# rocket_pack-compact.net
KiCad netlist of a schematic drawn in EAGLE
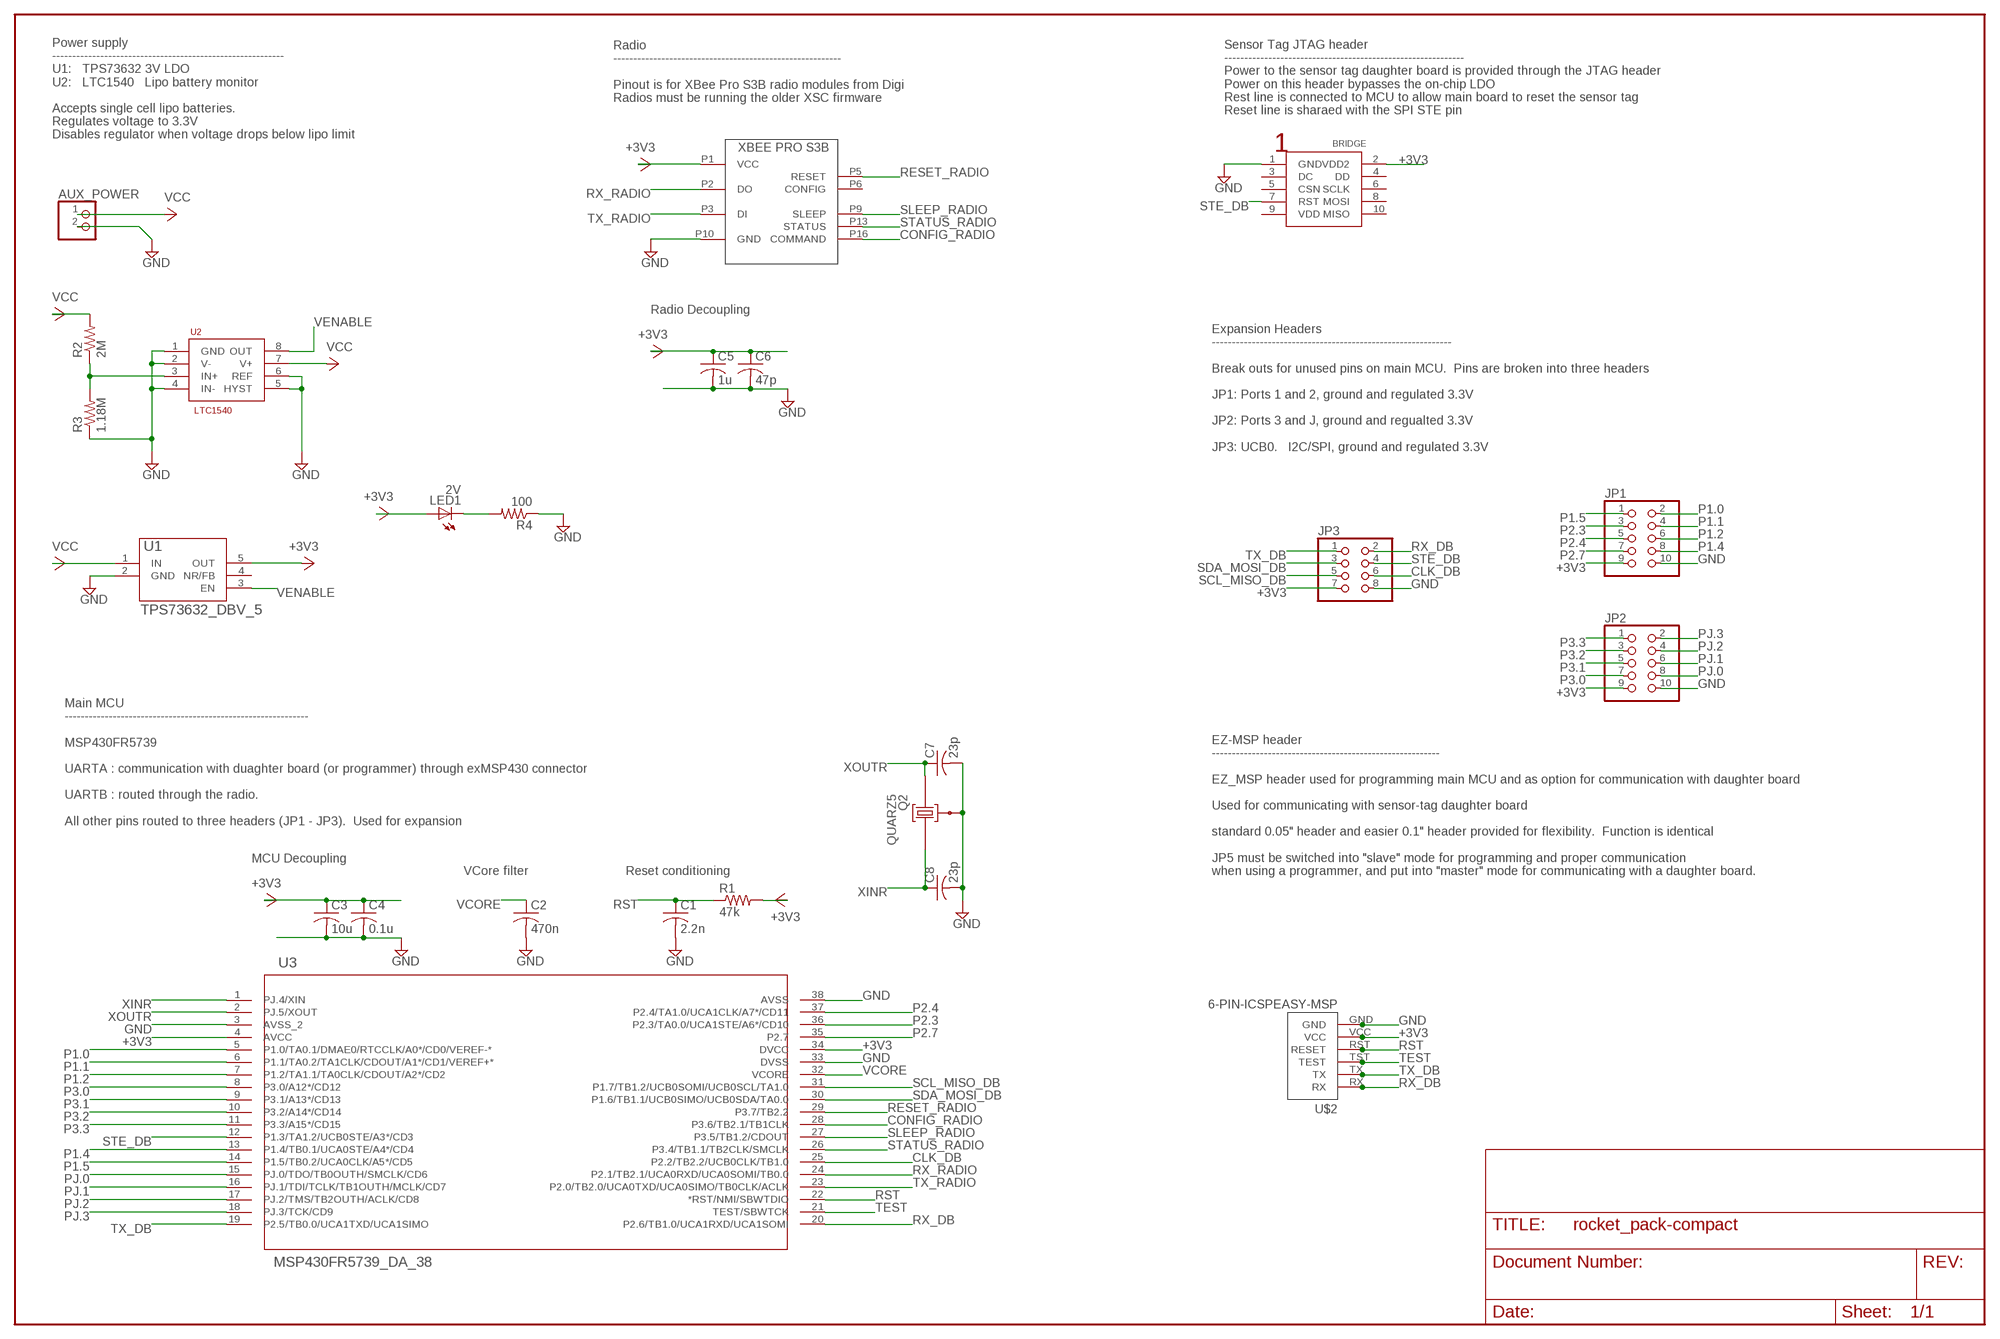
[diagram p0: schematic, sheet 1]

(export (version "E")
  (design (tool "Eeschema 10.0.6"))
  (components
    (comp (ref "AUX_POWER")
      (value "PINHD-1X2")
      (footprint "eagle-import:1X02")
      (libsource (lib "eagle-import") (part "PINHD-1X2"))
    )
    (comp (ref "BRIDGE")
      (value "CC-DEBUG")
      (footprint "eagle-import:2X5-1.27MM")
      (libsource (lib "eagle-import") (part "CC-DEBUG"))
    )
    (comp (ref "C1")
      (value "2.2n")
      (footprint "eagle-import:C1206")
      (libsource (lib "eagle-import") (part "C-USC1206"))
    )
    (comp (ref "C2")
      (value "470n")
      (footprint "eagle-import:C1206")
      (libsource (lib "eagle-import") (part "C-USC1206"))
    )
    (comp (ref "C3")
      (value "10u")
      (footprint "eagle-import:C1206")
      (libsource (lib "eagle-import") (part "C-USC1206"))
    )
    (comp (ref "C4")
      (value "0.1u")
      (footprint "eagle-import:C1206")
      (libsource (lib "eagle-import") (part "C-USC1206"))
    )
    (comp (ref "C5")
      (value "1u")
      (footprint "eagle-import:C1206")
      (libsource (lib "eagle-import") (part "C-USC1206"))
    )
    (comp (ref "C6")
      (value "47p")
      (footprint "eagle-import:C1206")
      (libsource (lib "eagle-import") (part "C-USC1206"))
    )
    (comp (ref "C7")
      (value "23p")
      (footprint "eagle-import:C1206")
      (libsource (lib "eagle-import") (part "C-USC1206"))
    )
    (comp (ref "C8")
      (value "23p")
      (footprint "eagle-import:C1206")
      (libsource (lib "eagle-import") (part "C-USC1206"))
    )
    (comp (ref "JP1")
      (value "PINHD-2X5")
      (footprint "eagle-import:2X05")
      (libsource (lib "eagle-import") (part "PINHD-2X5"))
    )
    (comp (ref "JP2")
      (value "PINHD-2X5")
      (footprint "eagle-import:2X05")
      (libsource (lib "eagle-import") (part "PINHD-2X5"))
    )
    (comp (ref "JP3")
      (value "PINHD-2X4")
      (footprint "eagle-import:2X04")
      (libsource (lib "eagle-import") (part "PINHD-2X4"))
    )
    (comp (ref "LED1")
      (value "2V")
      (footprint "eagle-import:1206")
      (libsource (lib "eagle-import") (part "LEDSMT1206"))
    )
    (comp (ref "Q2")
      (value "QUARZ5")
      (footprint "eagle-import:QUARZ5")
      (libsource (lib "eagle-import") (part "QUARZ5"))
    )
    (comp (ref "R1")
      (value "47k")
      (footprint "eagle-import:R1206")
      (libsource (lib "eagle-import") (part "R-US_R1206"))
    )
    (comp (ref "R2")
      (value "2M")
      (footprint "eagle-import:R1206")
      (libsource (lib "eagle-import") (part "R-US_R1206"))
    )
    (comp (ref "R3")
      (value "1.18M")
      (footprint "eagle-import:R1206")
      (libsource (lib "eagle-import") (part "R-US_R1206"))
    )
    (comp (ref "R4")
      (value "100")
      (footprint "eagle-import:R1206")
      (libsource (lib "eagle-import") (part "R-US_R1206"))
    )
    (comp (ref "U$1")
      (value "XBEE_PRO_S3B")
      (footprint "eagle-import:PRO_S3B")
      (libsource (lib "eagle-import") (part "XBEE_PRO_S3B"))
    )
    (comp (ref "U$2")
      (value "6-PIN-ICSPEASY-MSP")
      (footprint "eagle-import:EASYMSP-6PIN")
      (libsource (lib "eagle-import") (part "6-PIN-ICSPEASY-MSP"))
    )
    (comp (ref "U1")
      (value "TPS73632_DBV_5")
      (footprint "eagle-import:DBV5")
      (fields
        (field (name "GENERIC_PART_NUMBER") "TPS73632")
        (field (name "MANUFACTURER") "Texas Instruments")
        (field (name "MANUFACTURER_PART_NUMBER") "tps73632_dbv_5")
      )
      (libsource (lib "eagle-import") (part "TPS73632_DBV_5"))
    )
    (comp (ref "U2")
      (value "LTC1540")
      (footprint "eagle-import:S8")
      (libsource (lib "eagle-import") (part "LTC1540"))
    )
    (comp (ref "U3")
      (value "MSP430FR5739_DA_38")
      (footprint "eagle-import:DA38")
      (fields
        (field (name "GENERIC_PART_NUMBER") "MSP430FR5739")
        (field (name "MANUFACTURER") "Texas Instruments")
        (field (name "MANUFACTURER_PART_NUMBER") "msp430fr5739_da_38")
      )
      (libsource (lib "eagle-import") (part "MSP430FR5739_DA_38"))
    )
  )
  (nets
    (net (code "1") (name "+3V3") (class "Default")
      (node (ref "BRIDGE") (pin "2") (pinfunction "VDD2_2") (pintype "bidirectional"))
      (node (ref "C3") (pin "1") (pinfunction "1_1") (pintype "passive"))
      (node (ref "C4") (pin "1") (pinfunction "1_1") (pintype "passive"))
      (node (ref "C5") (pin "1") (pinfunction "1_1") (pintype "passive"))
      (node (ref "C6") (pin "1") (pinfunction "1_1") (pintype "passive"))
      (node (ref "JP1") (pin "9") (pinfunction "9_9") (pintype "passive"))
      (node (ref "JP2") (pin "9") (pinfunction "9_9") (pintype "passive"))
      (node (ref "JP3") (pin "7") (pinfunction "7_7") (pintype "passive"))
      (node (ref "LED1") (pin "A") (pinfunction "A_A") (pintype "passive"))
      (node (ref "R1") (pin "2") (pinfunction "2_2") (pintype "passive"))
      (node (ref "U$1") (pin "P1") (pinfunction "VCC_P1") (pintype "bidirectional"))
      (node (ref "U$2") (pin "VCC") (pinfunction "VCC_VCC") (pintype "bidirectional"))
      (node (ref "U1") (pin "5") (pinfunction "OUT_5") (pintype "output"))
      (node (ref "U3") (pin "34") (pinfunction "DVCC_34") (pintype "power_in"))
      (node (ref "U3") (pin "4") (pinfunction "AVCC_4") (pintype "power_in"))
    )
    (net (code "2") (name "/CLK_DB") (class "Default")
      (node (ref "JP3") (pin "6") (pinfunction "6_6") (pintype "passive"))
      (node (ref "U3") (pin "25") (pinfunction "P2.2/TB2.2/UCB0CLK/TB1.0_25") (pintype "bidirectional"))
    )
    (net (code "3") (name "/CONFIG_RADIO") (class "Default")
      (node (ref "U$1") (pin "P16") (pinfunction "COMMAND_P16") (pintype "bidirectional"))
      (node (ref "U3") (pin "28") (pinfunction "P3.6/TB2.1/TB1CLK_28") (pintype "bidirectional"))
    )
    (net (code "4") (name "/P1.0") (class "Default")
      (node (ref "JP1") (pin "2") (pinfunction "2_2") (pintype "passive"))
      (node (ref "U3") (pin "5") (pinfunction "P1.0/TA0.1/DMAE0/RTCCLK/A0*/CD0/VEREF-*_5") (pintype "bidirectional"))
    )
    (net (code "5") (name "/P1.1") (class "Default")
      (node (ref "JP1") (pin "4") (pinfunction "4_4") (pintype "passive"))
      (node (ref "U3") (pin "6") (pinfunction "P1.1/TA0.2/TA1CLK/CDOUT/A1*/CD1/VEREF+*_6") (pintype "bidirectional"))
    )
    (net (code "6") (name "/P1.2") (class "Default")
      (node (ref "JP1") (pin "6") (pinfunction "6_6") (pintype "passive"))
      (node (ref "U3") (pin "7") (pinfunction "P1.2/TA1.1/TA0CLK/CDOUT/A2*/CD2_7") (pintype "bidirectional"))
    )
    (net (code "7") (name "/P1.4") (class "Default")
      (node (ref "JP1") (pin "8") (pinfunction "8_8") (pintype "passive"))
      (node (ref "U3") (pin "13") (pinfunction "P1.4/TB0.1/UCA0STE/A4*/CD4_13") (pintype "bidirectional"))
    )
    (net (code "8") (name "/P1.5") (class "Default")
      (node (ref "JP1") (pin "1") (pinfunction "1_1") (pintype "passive"))
      (node (ref "U3") (pin "14") (pinfunction "P1.5/TB0.2/UCA0CLK/A5*/CD5_14") (pintype "bidirectional"))
    )
    (net (code "9") (name "/P2.3") (class "Default")
      (node (ref "JP1") (pin "3") (pinfunction "3_3") (pintype "passive"))
      (node (ref "U3") (pin "36") (pinfunction "P2.3/TA0.0/UCA1STE/A6*/CD10_36") (pintype "bidirectional"))
    )
    (net (code "10") (name "/P2.4") (class "Default")
      (node (ref "JP1") (pin "5") (pinfunction "5_5") (pintype "passive"))
      (node (ref "U3") (pin "37") (pinfunction "P2.4/TA1.0/UCA1CLK/A7*/CD11_37") (pintype "bidirectional"))
    )
    (net (code "11") (name "/P2.7") (class "Default")
      (node (ref "JP1") (pin "7") (pinfunction "7_7") (pintype "passive"))
      (node (ref "U3") (pin "35") (pinfunction "P2.7_35") (pintype "bidirectional"))
    )
    (net (code "12") (name "/P3.0") (class "Default")
      (node (ref "JP2") (pin "7") (pinfunction "7_7") (pintype "passive"))
      (node (ref "U3") (pin "8") (pinfunction "P3.0/A12*/CD12_8") (pintype "bidirectional"))
    )
    (net (code "13") (name "/P3.1") (class "Default")
      (node (ref "JP2") (pin "5") (pinfunction "5_5") (pintype "passive"))
      (node (ref "U3") (pin "9") (pinfunction "P3.1/A13*/CD13_9") (pintype "bidirectional"))
    )
    (net (code "14") (name "/P3.2") (class "Default")
      (node (ref "JP2") (pin "3") (pinfunction "3_3") (pintype "passive"))
      (node (ref "U3") (pin "10") (pinfunction "P3.2/A14*/CD14_10") (pintype "bidirectional"))
    )
    (net (code "15") (name "/P3.3") (class "Default")
      (node (ref "JP2") (pin "1") (pinfunction "1_1") (pintype "passive"))
      (node (ref "U3") (pin "11") (pinfunction "P3.3/A15*/CD15_11") (pintype "bidirectional"))
    )
    (net (code "16") (name "/PJ.0") (class "Default")
      (node (ref "JP2") (pin "8") (pinfunction "8_8") (pintype "passive"))
      (node (ref "U3") (pin "15") (pinfunction "PJ.0/TDO/TB0OUTH/SMCLK/CD6_15") (pintype "bidirectional"))
    )
    (net (code "17") (name "/PJ.1") (class "Default")
      (node (ref "JP2") (pin "6") (pinfunction "6_6") (pintype "passive"))
      (node (ref "U3") (pin "16") (pinfunction "PJ.1/TDI/TCLK/TB1OUTH/MCLK/CD7_16") (pintype "bidirectional"))
    )
    (net (code "18") (name "/PJ.2") (class "Default")
      (node (ref "JP2") (pin "4") (pinfunction "4_4") (pintype "passive"))
      (node (ref "U3") (pin "17") (pinfunction "PJ.2/TMS/TB2OUTH/ACLK/CD8_17") (pintype "bidirectional"))
    )
    (net (code "19") (name "/PJ.3") (class "Default")
      (node (ref "JP2") (pin "2") (pinfunction "2_2") (pintype "passive"))
      (node (ref "U3") (pin "18") (pinfunction "PJ.3/TCK/CD9_18") (pintype "bidirectional"))
    )
    (net (code "20") (name "/RESET_RADIO") (class "Default")
      (node (ref "U$1") (pin "P5") (pinfunction "RESET_P5") (pintype "bidirectional"))
      (node (ref "U3") (pin "29") (pinfunction "P3.7/TB2.2_29") (pintype "bidirectional"))
    )
    (net (code "21") (name "/RST") (class "Default")
      (node (ref "C1") (pin "1") (pinfunction "1_1") (pintype "passive"))
      (node (ref "R1") (pin "1") (pinfunction "1_1") (pintype "passive"))
      (node (ref "U$2") (pin "RST") (pinfunction "RESET_RST") (pintype "bidirectional"))
      (node (ref "U3") (pin "22") (pinfunction "*RST/NMI/SBWTDIO_22") (pintype "bidirectional"))
    )
    (net (code "22") (name "/RX_DB") (class "Default")
      (node (ref "JP3") (pin "2") (pinfunction "2_2") (pintype "passive"))
      (node (ref "U$2") (pin "RX") (pinfunction "RX_RX") (pintype "bidirectional"))
      (node (ref "U3") (pin "20") (pinfunction "P2.6/TB1.0/UCA1RXD/UCA1SOMI_20") (pintype "bidirectional"))
    )
    (net (code "23") (name "/RX_RADIO") (class "Default")
      (node (ref "U$1") (pin "P2") (pinfunction "DO_P2") (pintype "bidirectional"))
      (node (ref "U3") (pin "24") (pinfunction "P2.1/TB2.1/UCA0RXD/UCA0SOMI/TB0.0_24") (pintype "bidirectional"))
    )
    (net (code "24") (name "/SCL_MISO_DB") (class "Default")
      (node (ref "JP3") (pin "5") (pinfunction "5_5") (pintype "passive"))
      (node (ref "U3") (pin "31") (pinfunction "P1.7/TB1.2/UCB0SOMI/UCB0SCL/TA1.0_31") (pintype "bidirectional"))
    )
    (net (code "25") (name "/SDA_MOSI_DB") (class "Default")
      (node (ref "JP3") (pin "3") (pinfunction "3_3") (pintype "passive"))
      (node (ref "U3") (pin "30") (pinfunction "P1.6/TB1.1/UCB0SIMO/UCB0SDA/TA0.0_30") (pintype "bidirectional"))
    )
    (net (code "26") (name "/SLEEP_RADIO") (class "Default")
      (node (ref "U$1") (pin "P9") (pinfunction "SLEEP_P9") (pintype "bidirectional"))
      (node (ref "U3") (pin "27") (pinfunction "P3.5/TB1.2/CDOUT_27") (pintype "bidirectional"))
    )
    (net (code "27") (name "/STATUS_RADIO") (class "Default")
      (node (ref "U$1") (pin "P13") (pinfunction "STATUS_P13") (pintype "bidirectional"))
      (node (ref "U3") (pin "26") (pinfunction "P3.4/TB1.1/TB2CLK/SMCLK_26") (pintype "bidirectional"))
    )
    (net (code "28") (name "/STE_DB") (class "Default")
      (node (ref "BRIDGE") (pin "7") (pinfunction "RST_7") (pintype "bidirectional"))
      (node (ref "JP3") (pin "4") (pinfunction "4_4") (pintype "passive"))
      (node (ref "U3") (pin "12") (pinfunction "P1.3/TA1.2/UCB0STE/A3*/CD3_12") (pintype "bidirectional"))
    )
    (net (code "29") (name "/TEST") (class "Default")
      (node (ref "U$2") (pin "TST") (pinfunction "TEST_TST") (pintype "bidirectional"))
      (node (ref "U3") (pin "21") (pinfunction "TEST/SBWTCK_21") (pintype "bidirectional"))
    )
    (net (code "30") (name "/TX_DB") (class "Default")
      (node (ref "JP3") (pin "1") (pinfunction "1_1") (pintype "passive"))
      (node (ref "U$2") (pin "TX") (pinfunction "TX_TX") (pintype "bidirectional"))
      (node (ref "U3") (pin "19") (pinfunction "P2.5/TB0.0/UCA1TXD/UCA1SIMO_19") (pintype "bidirectional"))
    )
    (net (code "31") (name "/TX_RADIO") (class "Default")
      (node (ref "U$1") (pin "P3") (pinfunction "DI_P3") (pintype "bidirectional"))
      (node (ref "U3") (pin "23") (pinfunction "P2.0/TB2.0/UCA0TXD/UCA0SIMO/TB0CLK/ACLK_23") (pintype "bidirectional"))
    )
    (net (code "32") (name "/VCORE") (class "Default")
      (node (ref "C2") (pin "1") (pinfunction "1_1") (pintype "passive"))
      (node (ref "U3") (pin "32") (pinfunction "VCORE_32") (pintype "power_in"))
    )
    (net (code "33") (name "/VENABLE") (class "Default")
      (node (ref "U1") (pin "3") (pinfunction "EN_3") (pintype "passive"))
      (node (ref "U2") (pin "8") (pinfunction "OUT_8") (pintype "bidirectional"))
    )
    (net (code "34") (name "/XINR") (class "Default")
      (node (ref "C8") (pin "1") (pinfunction "1_1") (pintype "passive"))
      (node (ref "Q2") (pin "1") (pinfunction "1_1") (pintype "passive"))
      (node (ref "U3") (pin "1") (pinfunction "PJ.4/XIN_1") (pintype "bidirectional"))
    )
    (net (code "35") (name "/XOUTR") (class "Default")
      (node (ref "C7") (pin "1") (pinfunction "1_1") (pintype "passive"))
      (node (ref "Q2") (pin "2") (pinfunction "2_2") (pintype "passive"))
      (node (ref "U3") (pin "2") (pinfunction "PJ.5/XOUT_2") (pintype "bidirectional"))
    )
    (net (code "36") (name "GND") (class "Default")
      (node (ref "AUX_POWER") (pin "2") (pinfunction "2_2") (pintype "passive"))
      (node (ref "BRIDGE") (pin "1") (pinfunction "GND_1") (pintype "bidirectional"))
      (node (ref "C1") (pin "2") (pinfunction "2_2") (pintype "passive"))
      (node (ref "C2") (pin "2") (pinfunction "2_2") (pintype "passive"))
      (node (ref "C3") (pin "2") (pinfunction "2_2") (pintype "passive"))
      (node (ref "C4") (pin "2") (pinfunction "2_2") (pintype "passive"))
      (node (ref "C5") (pin "2") (pinfunction "2_2") (pintype "passive"))
      (node (ref "C6") (pin "2") (pinfunction "2_2") (pintype "passive"))
      (node (ref "C7") (pin "2") (pinfunction "2_2") (pintype "passive"))
      (node (ref "C8") (pin "2") (pinfunction "2_2") (pintype "passive"))
      (node (ref "JP1") (pin "10") (pinfunction "10_10") (pintype "passive"))
      (node (ref "JP2") (pin "10") (pinfunction "10_10") (pintype "passive"))
      (node (ref "JP3") (pin "8") (pinfunction "8_8") (pintype "passive"))
      (node (ref "Q2") (pin "GND@0") (pinfunction "0_GND@0") (pintype "passive"))
      (node (ref "R3") (pin "1") (pinfunction "1_1") (pintype "passive"))
      (node (ref "R4") (pin "1") (pinfunction "1_1") (pintype "passive"))
      (node (ref "U$1") (pin "P10") (pinfunction "GND_P10") (pintype "bidirectional"))
      (node (ref "U$2") (pin "GND") (pinfunction "GND_GND") (pintype "bidirectional"))
      (node (ref "U1") (pin "2") (pinfunction "GND_2") (pintype "power_in"))
      (node (ref "U2") (pin "1") (pinfunction "GND_1") (pintype "bidirectional"))
      (node (ref "U2") (pin "2") (pinfunction "V-_2") (pintype "bidirectional"))
      (node (ref "U2") (pin "4") (pinfunction "IN-_4") (pintype "bidirectional"))
      (node (ref "U2") (pin "5") (pinfunction "HYST_5") (pintype "bidirectional"))
      (node (ref "U2") (pin "6") (pinfunction "REF_6") (pintype "bidirectional"))
      (node (ref "U3") (pin "3") (pinfunction "AVSS_2_3") (pintype "power_in"))
      (node (ref "U3") (pin "33") (pinfunction "DVSS_33") (pintype "power_in"))
      (node (ref "U3") (pin "38") (pinfunction "AVSS_38") (pintype "power_in"))
    )
    (net (code "37") (name "Net-(LED1-PadC)") (class "Default")
      (node (ref "LED1") (pin "C") (pinfunction "C_C") (pintype "passive"))
      (node (ref "R4") (pin "2") (pinfunction "2_2") (pintype "passive"))
    )
    (net (code "38") (name "Net-(U2-IN+)") (class "Default")
      (node (ref "R2") (pin "1") (pinfunction "1_1") (pintype "passive"))
      (node (ref "R3") (pin "2") (pinfunction "2_2") (pintype "passive"))
      (node (ref "U2") (pin "3") (pinfunction "IN+_3") (pintype "bidirectional"))
    )
    (net (code "39") (name "VCC") (class "Default")
      (node (ref "AUX_POWER") (pin "1") (pinfunction "1_1") (pintype "passive"))
      (node (ref "R2") (pin "2") (pinfunction "2_2") (pintype "passive"))
      (node (ref "U1") (pin "1") (pinfunction "IN_1") (pintype "input"))
      (node (ref "U2") (pin "7") (pinfunction "V+_7") (pintype "bidirectional"))
    )
    (net (code "40") (name "unconnected-(BRIDGE-CSN-Pad5)") (class "Default")
      (node (ref "BRIDGE") (pin "5") (pinfunction "CSN_5") (pintype "bidirectional"))
    )
    (net (code "41") (name "unconnected-(BRIDGE-DC-Pad3)") (class "Default")
      (node (ref "BRIDGE") (pin "3") (pinfunction "DC_3") (pintype "bidirectional"))
    )
    (net (code "42") (name "unconnected-(BRIDGE-DD-Pad4)") (class "Default")
      (node (ref "BRIDGE") (pin "4") (pinfunction "DD_4") (pintype "bidirectional"))
    )
    (net (code "43") (name "unconnected-(BRIDGE-MISO-Pad10)") (class "Default")
      (node (ref "BRIDGE") (pin "10") (pinfunction "MISO_10") (pintype "bidirectional"))
    )
    (net (code "44") (name "unconnected-(BRIDGE-MOSI-Pad8)") (class "Default")
      (node (ref "BRIDGE") (pin "8") (pinfunction "MOSI_8") (pintype "bidirectional"))
    )
    (net (code "45") (name "unconnected-(BRIDGE-SCLK-Pad6)") (class "Default")
      (node (ref "BRIDGE") (pin "6") (pinfunction "SCLK_6") (pintype "bidirectional"))
    )
    (net (code "46") (name "unconnected-(BRIDGE-VDD-Pad9)") (class "Default")
      (node (ref "BRIDGE") (pin "9") (pinfunction "VDD_9") (pintype "bidirectional"))
    )
    (net (code "47") (name "unconnected-(U$1-CONFIG-PadP6)") (class "Default")
      (node (ref "U$1") (pin "P6") (pinfunction "CONFIG_P6") (pintype "bidirectional"))
    )
    (net (code "48") (name "unconnected-(U1-NR{slash}FB-Pad4)") (class "Default")
      (node (ref "U1") (pin "4") (pinfunction "NR/FB_4") (pintype "bidirectional"))
    )
  )
)
